# Connectors.net
KiCad netlist of a schematic drawn in Altium Designer
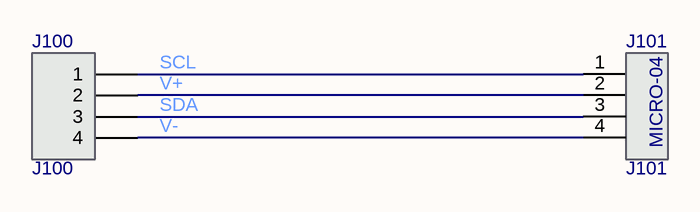
[diagram p0: Connectors.SchDoc]

(export (version "E")
  (design (tool "Eeschema 10.0.6"))
  (components
    (comp (ref "J100")
      (value "RRC-MC11-90-2")
      (footprint "RRC-MC11-90-2")
      (description "Connector")
      (fields (field (name "MF") "RRC Power Solutions"))
      (libsource (lib "Database_Libs1") (part "RRC-MC11-90-2"))
    )
    (comp (ref "J101")
      (value "MICRO-04 RIGHT-ANGLE")
      (footprint "MICRO-04 RIGHT")
      (description "Connector")
      (fields (field (name "MANUFACTURER") "Molex") (field (name "MANUFACTURER PART NUMBER") "53261-0471"))
      (libsource (lib "Database_Libs1") (part "MICRO-04"))
    )
  )
  (nets
    (net (code "1") (name "/SCL") (class "Default")
      (node (ref "J100") (pin "1") (pinfunction "1_1") (pintype "passive"))
      (node (ref "J101") (pin "1") (pinfunction "1_1") (pintype "passive"))
    )
    (net (code "2") (name "/SDA") (class "Default")
      (node (ref "J100") (pin "3") (pinfunction "3_3") (pintype "passive"))
      (node (ref "J101") (pin "3") (pinfunction "3_3") (pintype "passive"))
    )
    (net (code "3") (name "/V+") (class "Default")
      (node (ref "J100") (pin "2") (pinfunction "2_2") (pintype "passive"))
      (node (ref "J101") (pin "2") (pinfunction "2_2") (pintype "passive"))
    )
    (net (code "4") (name "/V-") (class "Default")
      (node (ref "J100") (pin "4") (pinfunction "4_4") (pintype "passive"))
      (node (ref "J101") (pin "4") (pinfunction "4_4") (pintype "passive"))
    )
  )
)
